# CE842170047_SHEET6.net
KiCad netlist of a schematic drawn in Altium Designer
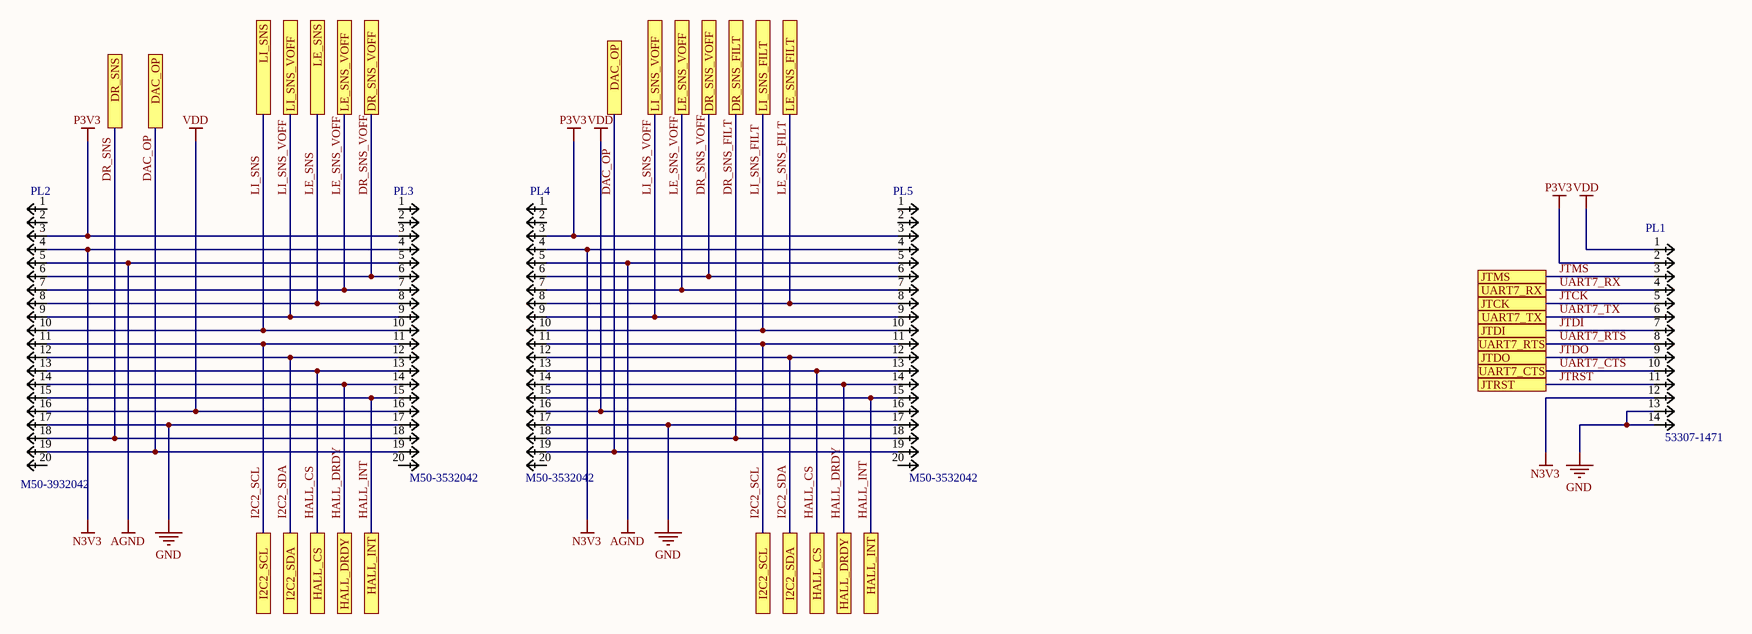
[diagram p0: CE842170047_SHEET6.SchDoc]

(export (version "E")
  (design (tool "Eeschema 10.0.6"))
  (components
    (comp (ref "PL1")
      (value "KK/96510/1748")
      (footprint "53307-1471")
      (description "PLUG HEADER 2x7WAY STRAIGHT MOLEX")
      (fields (field (name "MF_PARTNUMBER") "53307-1471") (field (name "MANUFACTURER") "MOLEX"))
      (libsource (lib "AltiumComponents") (part "CONN_PL_2x7"))
    )
    (comp (ref "PL2")
      (value "KK/96510/2206")
      (footprint "M50-3932042")
      (description "PLUG 20WAY RIGHT ANGLE PTH HARWIN")
      (fields (field (name "MF_PARTNUMBER") "M50-3932042") (field (name "MANUFACTURER") "HARWIN"))
      (libsource (lib "AltiumComponents") (part "CONN_PL_1x20"))
    )
    (comp (ref "PL3")
      (value "KK/96510/2208")
      (footprint "M50-3532042")
      (description "PLUG,20WAY,STRAIGHT,PITCH 1.27MM,HWN,M50-3532042")
      (fields (field (name "MF_PARTNUMBER") "M50-3532042") (field (name "MANUFACTURER") "HARWIN"))
      (libsource (lib "AltiumComponents") (part "CONN_PL_1x20"))
    )
    (comp (ref "PL4")
      (value "KK/96510/2208")
      (footprint "M50-3532042")
      (description "PLUG,20WAY,STRAIGHT,PITCH 1.27MM,HWN,M50-3532042")
      (fields (field (name "MF_PARTNUMBER") "M50-3532042") (field (name "MANUFACTURER") "HARWIN"))
      (libsource (lib "AltiumComponents") (part "CONN_PL_1x20"))
    )
    (comp (ref "PL5")
      (value "KK/96510/2208")
      (footprint "M50-3532042")
      (description "PLUG,20WAY,STRAIGHT,PITCH 1.27MM,HWN,M50-3532042")
      (fields (field (name "MF_PARTNUMBER") "M50-3532042") (field (name "MANUFACTURER") "HARWIN"))
      (libsource (lib "AltiumComponents") (part "CONN_PL_1x20"))
    )
  )
  (nets
    (net (code "1") (name "/DAC_OP") (class "Default")
      (node (ref "PL2") (pin "19") (pinfunction "19_19") (pintype "passive"))
      (node (ref "PL3") (pin "19") (pinfunction "19_19") (pintype "passive"))
      (node (ref "PL4") (pin "19") (pinfunction "19_19") (pintype "passive"))
      (node (ref "PL5") (pin "19") (pinfunction "19_19") (pintype "passive"))
    )
    (net (code "2") (name "/DR_SNS") (class "Default")
      (node (ref "PL2") (pin "18") (pinfunction "18_18") (pintype "passive"))
      (node (ref "PL3") (pin "18") (pinfunction "18_18") (pintype "passive"))
    )
    (net (code "3") (name "/DR_SNS_FILT") (class "Default")
      (node (ref "PL4") (pin "18") (pinfunction "18_18") (pintype "passive"))
      (node (ref "PL5") (pin "18") (pinfunction "18_18") (pintype "passive"))
    )
    (net (code "4") (name "/DR_SNS_VOFF") (class "Default")
      (node (ref "PL2") (pin "6") (pinfunction "6_6") (pintype "passive"))
      (node (ref "PL3") (pin "6") (pinfunction "6_6") (pintype "passive"))
      (node (ref "PL4") (pin "6") (pinfunction "6_6") (pintype "passive"))
      (node (ref "PL5") (pin "6") (pinfunction "6_6") (pintype "passive"))
    )
    (net (code "5") (name "/HALL_CS") (class "Default")
      (node (ref "PL2") (pin "13") (pinfunction "13_13") (pintype "passive"))
      (node (ref "PL3") (pin "13") (pinfunction "13_13") (pintype "passive"))
      (node (ref "PL4") (pin "13") (pinfunction "13_13") (pintype "passive"))
      (node (ref "PL5") (pin "13") (pinfunction "13_13") (pintype "passive"))
    )
    (net (code "6") (name "/HALL_DRDY") (class "Default")
      (node (ref "PL2") (pin "14") (pinfunction "14_14") (pintype "passive"))
      (node (ref "PL3") (pin "14") (pinfunction "14_14") (pintype "passive"))
      (node (ref "PL4") (pin "14") (pinfunction "14_14") (pintype "passive"))
      (node (ref "PL5") (pin "14") (pinfunction "14_14") (pintype "passive"))
    )
    (net (code "7") (name "/HALL_INT") (class "Default")
      (node (ref "PL2") (pin "15") (pinfunction "15_15") (pintype "passive"))
      (node (ref "PL3") (pin "15") (pinfunction "15_15") (pintype "passive"))
      (node (ref "PL4") (pin "15") (pinfunction "15_15") (pintype "passive"))
      (node (ref "PL5") (pin "15") (pinfunction "15_15") (pintype "passive"))
    )
    (net (code "8") (name "/I2C2_SCL") (class "Default")
      (node (ref "PL2") (pin "11") (pinfunction "11_11") (pintype "passive"))
      (node (ref "PL3") (pin "11") (pinfunction "11_11") (pintype "passive"))
      (node (ref "PL4") (pin "11") (pinfunction "11_11") (pintype "passive"))
      (node (ref "PL5") (pin "11") (pinfunction "11_11") (pintype "passive"))
    )
    (net (code "9") (name "/I2C2_SDA") (class "Default")
      (node (ref "PL2") (pin "12") (pinfunction "12_12") (pintype "passive"))
      (node (ref "PL3") (pin "12") (pinfunction "12_12") (pintype "passive"))
      (node (ref "PL4") (pin "12") (pinfunction "12_12") (pintype "passive"))
      (node (ref "PL5") (pin "12") (pinfunction "12_12") (pintype "passive"))
    )
    (net (code "10") (name "/JTCK") (class "Default")
      (node (ref "PL1") (pin "5") (pinfunction "5_5") (pintype "passive"))
    )
    (net (code "11") (name "/JTDI") (class "Default")
      (node (ref "PL1") (pin "7") (pinfunction "7_7") (pintype "passive"))
    )
    (net (code "12") (name "/JTDO") (class "Default")
      (node (ref "PL1") (pin "9") (pinfunction "9_9") (pintype "passive"))
    )
    (net (code "13") (name "/JTMS") (class "Default")
      (node (ref "PL1") (pin "3") (pinfunction "3_3") (pintype "passive"))
    )
    (net (code "14") (name "/JTRST") (class "Default")
      (node (ref "PL1") (pin "11") (pinfunction "11_11") (pintype "passive"))
    )
    (net (code "15") (name "/LE_SNS") (class "Default")
      (node (ref "PL2") (pin "8") (pinfunction "8_8") (pintype "passive"))
      (node (ref "PL3") (pin "8") (pinfunction "8_8") (pintype "passive"))
    )
    (net (code "16") (name "/LE_SNS_FILT") (class "Default")
      (node (ref "PL4") (pin "8") (pinfunction "8_8") (pintype "passive"))
      (node (ref "PL5") (pin "8") (pinfunction "8_8") (pintype "passive"))
    )
    (net (code "17") (name "/LE_SNS_VOFF") (class "Default")
      (node (ref "PL2") (pin "7") (pinfunction "7_7") (pintype "passive"))
      (node (ref "PL3") (pin "7") (pinfunction "7_7") (pintype "passive"))
      (node (ref "PL4") (pin "7") (pinfunction "7_7") (pintype "passive"))
      (node (ref "PL5") (pin "7") (pinfunction "7_7") (pintype "passive"))
    )
    (net (code "18") (name "/LI_SNS") (class "Default")
      (node (ref "PL2") (pin "10") (pinfunction "10_10") (pintype "passive"))
      (node (ref "PL3") (pin "10") (pinfunction "10_10") (pintype "passive"))
    )
    (net (code "19") (name "/LI_SNS_FILT") (class "Default")
      (node (ref "PL4") (pin "10") (pinfunction "10_10") (pintype "passive"))
      (node (ref "PL5") (pin "10") (pinfunction "10_10") (pintype "passive"))
    )
    (net (code "20") (name "/LI_SNS_VOFF") (class "Default")
      (node (ref "PL2") (pin "9") (pinfunction "9_9") (pintype "passive"))
      (node (ref "PL3") (pin "9") (pinfunction "9_9") (pintype "passive"))
      (node (ref "PL4") (pin "9") (pinfunction "9_9") (pintype "passive"))
      (node (ref "PL5") (pin "9") (pinfunction "9_9") (pintype "passive"))
    )
    (net (code "21") (name "/UART7_CTS") (class "Default")
      (node (ref "PL1") (pin "10") (pinfunction "10_10") (pintype "passive"))
    )
    (net (code "22") (name "/UART7_RTS") (class "Default")
      (node (ref "PL1") (pin "8") (pinfunction "8_8") (pintype "passive"))
    )
    (net (code "23") (name "/UART7_RX") (class "Default")
      (node (ref "PL1") (pin "4") (pinfunction "4_4") (pintype "passive"))
    )
    (net (code "24") (name "/UART7_TX") (class "Default")
      (node (ref "PL1") (pin "6") (pinfunction "6_6") (pintype "passive"))
    )
    (net (code "25") (name "AGND") (class "Default")
      (node (ref "PL2") (pin "5") (pinfunction "5_5") (pintype "passive"))
      (node (ref "PL3") (pin "5") (pinfunction "5_5") (pintype "passive"))
      (node (ref "PL4") (pin "5") (pinfunction "5_5") (pintype "passive"))
      (node (ref "PL5") (pin "5") (pinfunction "5_5") (pintype "passive"))
    )
    (net (code "26") (name "GND") (class "Default")
      (node (ref "PL1") (pin "13") (pinfunction "13_13") (pintype "passive"))
      (node (ref "PL1") (pin "14") (pinfunction "14_14") (pintype "passive"))
      (node (ref "PL2") (pin "17") (pinfunction "17_17") (pintype "passive"))
      (node (ref "PL3") (pin "17") (pinfunction "17_17") (pintype "passive"))
      (node (ref "PL4") (pin "17") (pinfunction "17_17") (pintype "passive"))
      (node (ref "PL5") (pin "17") (pinfunction "17_17") (pintype "passive"))
    )
    (net (code "27") (name "N3V3") (class "Default")
      (node (ref "PL1") (pin "12") (pinfunction "12_12") (pintype "passive"))
      (node (ref "PL2") (pin "4") (pinfunction "4_4") (pintype "passive"))
      (node (ref "PL3") (pin "4") (pinfunction "4_4") (pintype "passive"))
      (node (ref "PL4") (pin "4") (pinfunction "4_4") (pintype "passive"))
      (node (ref "PL5") (pin "4") (pinfunction "4_4") (pintype "passive"))
    )
    (net (code "28") (name "P3V3") (class "Default")
      (node (ref "PL1") (pin "2") (pinfunction "2_2") (pintype "passive"))
      (node (ref "PL2") (pin "3") (pinfunction "3_3") (pintype "passive"))
      (node (ref "PL3") (pin "3") (pinfunction "3_3") (pintype "passive"))
      (node (ref "PL4") (pin "3") (pinfunction "3_3") (pintype "passive"))
      (node (ref "PL5") (pin "3") (pinfunction "3_3") (pintype "passive"))
    )
    (net (code "29") (name "VDD") (class "Default")
      (node (ref "PL1") (pin "1") (pinfunction "1_1") (pintype "passive"))
      (node (ref "PL2") (pin "16") (pinfunction "16_16") (pintype "passive"))
      (node (ref "PL3") (pin "16") (pinfunction "16_16") (pintype "passive"))
      (node (ref "PL4") (pin "16") (pinfunction "16_16") (pintype "passive"))
      (node (ref "PL5") (pin "16") (pinfunction "16_16") (pintype "passive"))
    )
    (net (code "30") (name "unconnected-(PL2-Pad1)") (class "Default")
      (node (ref "PL2") (pin "1") (pinfunction "1_1") (pintype "passive"))
    )
    (net (code "31") (name "unconnected-(PL2-Pad2)") (class "Default")
      (node (ref "PL2") (pin "2") (pinfunction "2_2") (pintype "passive"))
    )
    (net (code "32") (name "unconnected-(PL2-Pad20)") (class "Default")
      (node (ref "PL2") (pin "20") (pinfunction "20_20") (pintype "passive"))
    )
    (net (code "33") (name "unconnected-(PL3-Pad1)") (class "Default")
      (node (ref "PL3") (pin "1") (pinfunction "1_1") (pintype "passive"))
    )
    (net (code "34") (name "unconnected-(PL3-Pad2)") (class "Default")
      (node (ref "PL3") (pin "2") (pinfunction "2_2") (pintype "passive"))
    )
    (net (code "35") (name "unconnected-(PL3-Pad20)") (class "Default")
      (node (ref "PL3") (pin "20") (pinfunction "20_20") (pintype "passive"))
    )
    (net (code "36") (name "unconnected-(PL4-Pad1)") (class "Default")
      (node (ref "PL4") (pin "1") (pinfunction "1_1") (pintype "passive"))
    )
    (net (code "37") (name "unconnected-(PL4-Pad2)") (class "Default")
      (node (ref "PL4") (pin "2") (pinfunction "2_2") (pintype "passive"))
    )
    (net (code "38") (name "unconnected-(PL4-Pad20)") (class "Default")
      (node (ref "PL4") (pin "20") (pinfunction "20_20") (pintype "passive"))
    )
    (net (code "39") (name "unconnected-(PL5-Pad1)") (class "Default")
      (node (ref "PL5") (pin "1") (pinfunction "1_1") (pintype "passive"))
    )
    (net (code "40") (name "unconnected-(PL5-Pad2)") (class "Default")
      (node (ref "PL5") (pin "2") (pinfunction "2_2") (pintype "passive"))
    )
    (net (code "41") (name "unconnected-(PL5-Pad20)") (class "Default")
      (node (ref "PL5") (pin "20") (pinfunction "20_20") (pintype "passive"))
    )
  )
)
